# pwm_driver.net
KiCad netlist of a schematic drawn in EAGLE
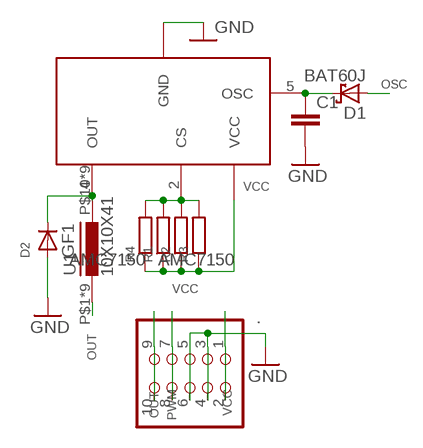
[diagram p0: schematic, sheet 1]

(export (version "E")
  (design (tool "Eeschema 10.0.6"))
  (components
    (comp (ref ".")
      (value "PINHD-2X5")
      (footprint "eagle-import:2X05")
      (libsource (lib "eagle-import") (part "PINHD-2X5"))
    )
    (comp (ref "AMC7150")
      (value "AMC7150")
      (footprint "eagle-import:TO-252-5L")
      (libsource (lib "eagle-import") (part "AMC7150"))
    )
    (comp (ref "C1")
      (value "C-EU025-024X044")
      (footprint "eagle-import:C025-024X044")
      (libsource (lib "eagle-import") (part "C-EU025-024X044"))
    )
    (comp (ref "D1")
      (value "BAT60J")
      (footprint "eagle-import:SOD323_ST")
      (libsource (lib "eagle-import") (part "BAT60J"))
    )
    (comp (ref "D2")
      (value "GF1")
      (footprint "eagle-import:SMA-DO214AC")
      (libsource (lib "eagle-import") (part "GF1"))
    )
    (comp (ref "R1")
      (value "R-EU_R1206")
      (footprint "eagle-import:R1206")
      (libsource (lib "eagle-import") (part "R-EU_R1206"))
    )
    (comp (ref "R2")
      (value "R-EU_R1206")
      (footprint "eagle-import:R1206")
      (libsource (lib "eagle-import") (part "R-EU_R1206"))
    )
    (comp (ref "R3")
      (value "R-EU_R1206")
      (footprint "eagle-import:R1206")
      (libsource (lib "eagle-import") (part "R-EU_R1206"))
    )
    (comp (ref "R4")
      (value "R-EU_R1206")
      (footprint "eagle-import:R1206")
      (libsource (lib "eagle-import") (part "R-EU_R1206"))
    )
    (comp (ref "U1")
      (value "10X10X41")
      (footprint "eagle-import:10X10X4")
      (libsource (lib "eagle-import") (part "10X10X41"))
    )
  )
  (nets
    (net (code "1") (name "/OSC") (class "Default")
      (node (ref "AMC7150") (pin "5") (pinfunction "OSC_5") (pintype "bidirectional"))
      (node (ref "C1") (pin "1") (pinfunction "1_1") (pintype "passive"))
      (node (ref "D1") (pin "C") (pinfunction "C_C") (pintype "passive"))
    )
    (net (code "2") (name "/OUT") (class "Default")
      (node (ref ".") (pin "10") (pinfunction "10_10") (pintype "passive"))
      (node (ref ".") (pin "9") (pinfunction "9_9") (pintype "passive"))
      (node (ref "U1") (pin "P$1") (pinfunction "1_P$1") (pintype "passive"))
      (node (ref "U1") (pin "P$2") (pinfunction "1_P$2") (pintype "passive"))
      (node (ref "U1") (pin "P$3") (pinfunction "1_P$3") (pintype "passive"))
      (node (ref "U1") (pin "P$4") (pinfunction "1_P$4") (pintype "passive"))
      (node (ref "U1") (pin "P$5") (pinfunction "1_P$5") (pintype "passive"))
      (node (ref "U1") (pin "P$6") (pinfunction "1_P$6") (pintype "passive"))
      (node (ref "U1") (pin "P$7") (pinfunction "1_P$7") (pintype "passive"))
      (node (ref "U1") (pin "P$8") (pinfunction "1_P$8") (pintype "passive"))
      (node (ref "U1") (pin "P$9") (pinfunction "1_P$9") (pintype "passive"))
    )
    (net (code "3") (name "/PWM") (class "Default")
      (node (ref ".") (pin "7") (pinfunction "7_7") (pintype "passive"))
      (node (ref ".") (pin "8") (pinfunction "8_8") (pintype "passive"))
      (node (ref "D1") (pin "A") (pinfunction "A_A") (pintype "passive"))
    )
    (net (code "4") (name "/VCC") (class "Default")
      (node (ref ".") (pin "1") (pinfunction "1_1") (pintype "passive"))
      (node (ref ".") (pin "2") (pinfunction "2_2") (pintype "passive"))
      (node (ref "AMC7150") (pin "1") (pinfunction "VCC_1") (pintype "power_in"))
      (node (ref "R1") (pin "1") (pinfunction "1_1") (pintype "passive"))
      (node (ref "R2") (pin "1") (pinfunction "1_1") (pintype "passive"))
      (node (ref "R3") (pin "1") (pinfunction "1_1") (pintype "passive"))
      (node (ref "R4") (pin "1") (pinfunction "1_1") (pintype "passive"))
    )
    (net (code "5") (name "GND") (class "Default")
      (node (ref ".") (pin "3") (pinfunction "3_3") (pintype "passive"))
      (node (ref ".") (pin "4") (pinfunction "4_4") (pintype "passive"))
      (node (ref ".") (pin "5") (pinfunction "5_5") (pintype "passive"))
      (node (ref ".") (pin "6") (pinfunction "6_6") (pintype "passive"))
      (node (ref "AMC7150") (pin "3") (pinfunction "GND_3") (pintype "power_in"))
      (node (ref "AMC7150") (pin "TAB") (pinfunction "GND_TAB") (pintype "power_in"))
      (node (ref "C1") (pin "2") (pinfunction "2_2") (pintype "passive"))
      (node (ref "D2") (pin "A") (pinfunction "A_A") (pintype "passive"))
    )
    (net (code "6") (name "Net-(AMC7150-CS)") (class "Default")
      (node (ref "AMC7150") (pin "2") (pinfunction "CS_2") (pintype "output"))
      (node (ref "R1") (pin "2") (pinfunction "2_2") (pintype "passive"))
      (node (ref "R2") (pin "2") (pinfunction "2_2") (pintype "passive"))
      (node (ref "R3") (pin "2") (pinfunction "2_2") (pintype "passive"))
      (node (ref "R4") (pin "2") (pinfunction "2_2") (pintype "passive"))
    )
    (net (code "7") (name "Net-(AMC7150-OUT)") (class "Default")
      (node (ref "AMC7150") (pin "4") (pinfunction "OUT_4") (pintype "output"))
      (node (ref "D2") (pin "K") (pinfunction "C_K") (pintype "passive"))
      (node (ref "U1") (pin "P$10") (pinfunction "2_P$10") (pintype "passive"))
      (node (ref "U1") (pin "P$11") (pinfunction "2_P$11") (pintype "passive"))
      (node (ref "U1") (pin "P$12") (pinfunction "2_P$12") (pintype "passive"))
      (node (ref "U1") (pin "P$13") (pinfunction "2_P$13") (pintype "passive"))
      (node (ref "U1") (pin "P$14") (pinfunction "2_P$14") (pintype "passive"))
      (node (ref "U1") (pin "P$15") (pinfunction "2_P$15") (pintype "passive"))
      (node (ref "U1") (pin "P$16") (pinfunction "2_P$16") (pintype "passive"))
      (node (ref "U1") (pin "P$17") (pinfunction "2_P$17") (pintype "passive"))
      (node (ref "U1") (pin "P$18") (pinfunction "2_P$18") (pintype "passive"))
    )
  )
)
